# rx.net
KiCad netlist of a schematic drawn in EAGLE
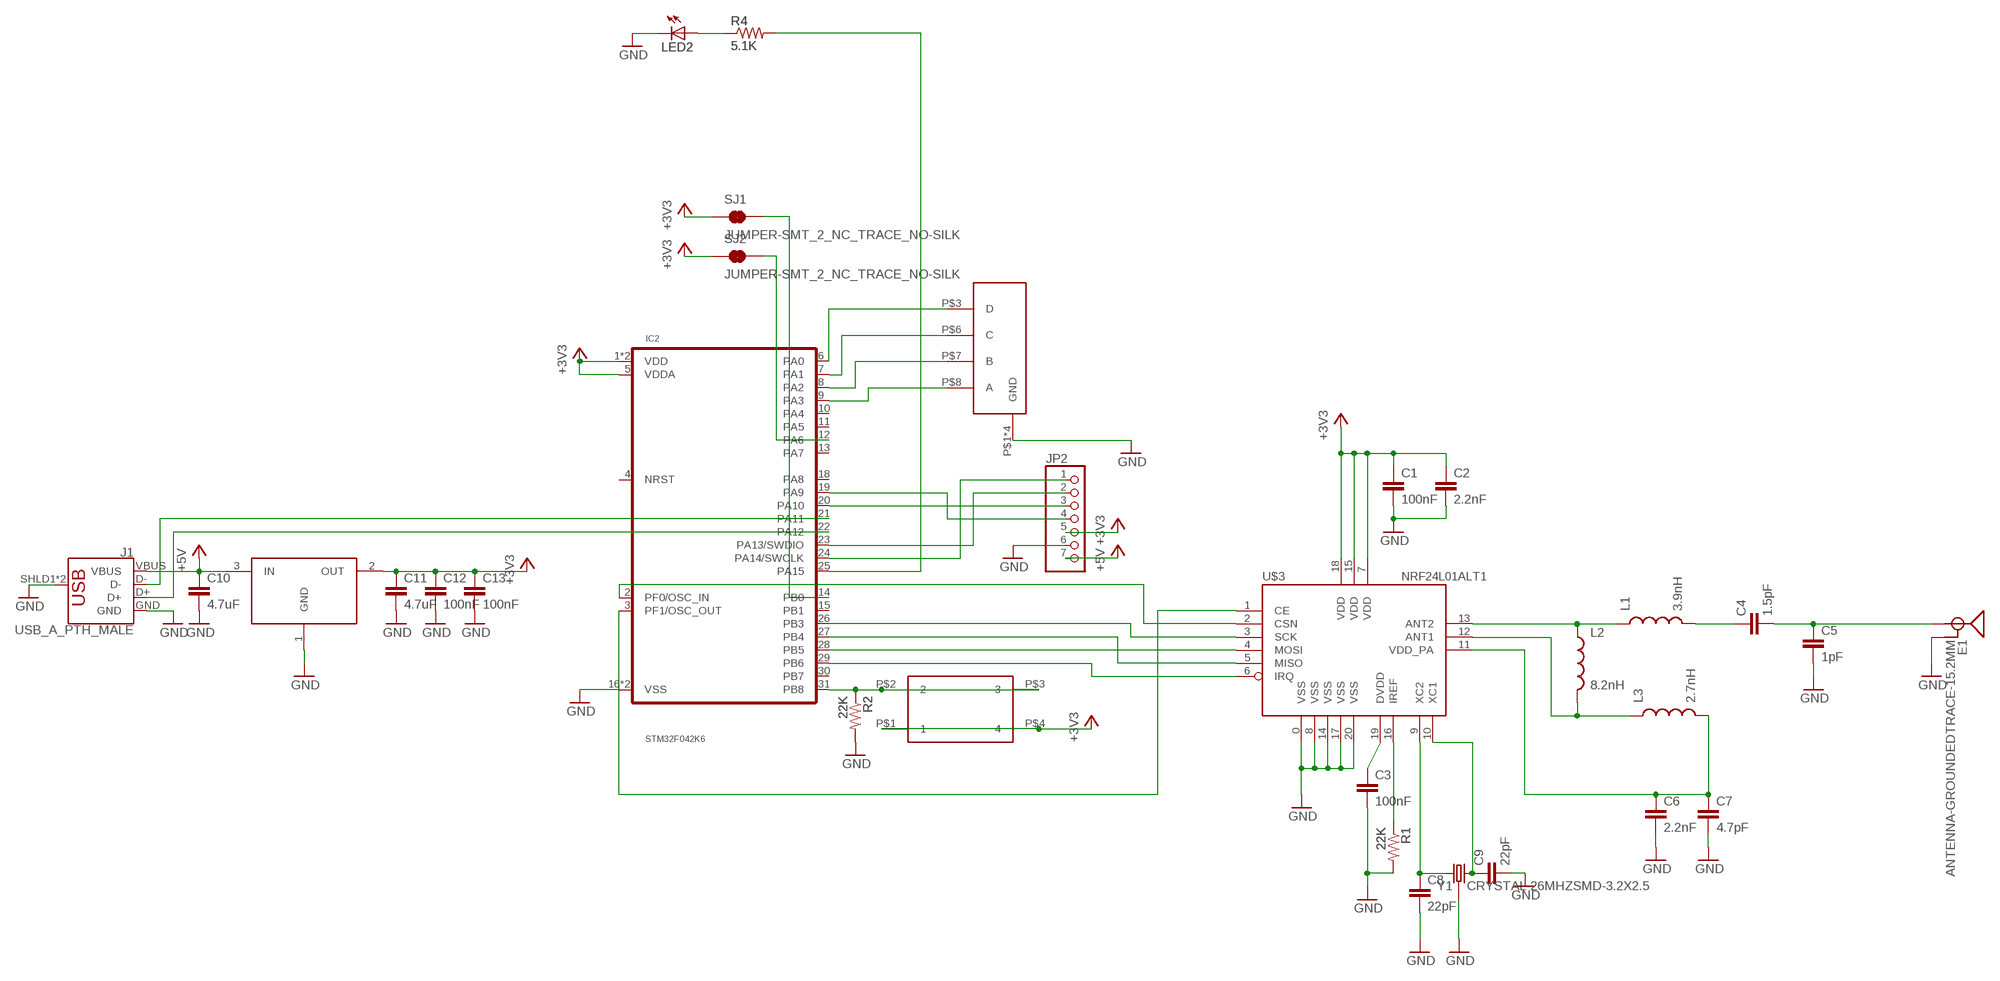
[diagram p0: schematic, sheet 1]

(export (version "E")
  (design (tool "Eeschema 10.0.6"))
  (components
    (comp (ref "C1")
      (value "100nF")
      (footprint "eagle-import:0805")
      (libsource (lib "eagle-import") (part "CAP0805"))
    )
    (comp (ref "C2")
      (value "2.2nF")
      (footprint "eagle-import:0805")
      (libsource (lib "eagle-import") (part "CAP0805"))
    )
    (comp (ref "C3")
      (value "100nF")
      (footprint "eagle-import:0805")
      (libsource (lib "eagle-import") (part "CAP0805"))
    )
    (comp (ref "C4")
      (value "1.5pF")
      (footprint "eagle-import:0805")
      (libsource (lib "eagle-import") (part "CAP0805"))
    )
    (comp (ref "C5")
      (value "1pF")
      (footprint "eagle-import:0805")
      (libsource (lib "eagle-import") (part "CAP0805"))
    )
    (comp (ref "C6")
      (value "2.2nF")
      (footprint "eagle-import:0805")
      (libsource (lib "eagle-import") (part "CAP0805"))
    )
    (comp (ref "C7")
      (value "4.7pF")
      (footprint "eagle-import:0805")
      (libsource (lib "eagle-import") (part "CAP0805"))
    )
    (comp (ref "C8")
      (value "22pF")
      (footprint "eagle-import:0805")
      (libsource (lib "eagle-import") (part "CAP0805"))
    )
    (comp (ref "C9")
      (value "22pF")
      (footprint "eagle-import:0805")
      (libsource (lib "eagle-import") (part "CAP0805"))
    )
    (comp (ref "C10")
      (value "4.7uF")
      (footprint "eagle-import:0805")
      (libsource (lib "eagle-import") (part "CAP0805"))
    )
    (comp (ref "C11")
      (value "4.7uF")
      (footprint "eagle-import:0805")
      (libsource (lib "eagle-import") (part "CAP0805"))
    )
    (comp (ref "C12")
      (value "100nF")
      (footprint "eagle-import:0805")
      (libsource (lib "eagle-import") (part "CAP0805"))
    )
    (comp (ref "C13")
      (value "100nF")
      (footprint "eagle-import:0805")
      (libsource (lib "eagle-import") (part "CAP0805"))
    )
    (comp (ref "E1")
      (value "ANTENNA-GROUNDEDTRACE-15.2MM")
      (footprint "eagle-import:TRACE_ANTENNA_2.4GHZ_15.2MM")
      (libsource (lib "eagle-import") (part "ANTENNA-GROUNDEDTRACE-15.2MM"))
    )
    (comp (ref "IC2")
      (value "STM32F042K6")
      (footprint "eagle-import:TQFP32-08")
      (libsource (lib "eagle-import") (part "STM32F042K6"))
    )
    (comp (ref "J1")
      (value "USB_A_PTH_MALE")
      (footprint "eagle-import:USB-A-H")
      (libsource (lib "eagle-import") (part "USB_A_PTH_MALE"))
    )
    (comp (ref "JP2")
      (value "PINHD-1X8CLEANBIG")
      (footprint "eagle-import:1X08-CLEANBIG")
      (libsource (lib "eagle-import") (part "PINHD-1X8CLEANBIG"))
    )
    (comp (ref "L1")
      (value "3.9nH")
      (footprint "eagle-import:0805")
      (libsource (lib "eagle-import") (part "INDUCTOR0805"))
    )
    (comp (ref "L2")
      (value "8.2nH")
      (footprint "eagle-import:0805")
      (libsource (lib "eagle-import") (part "INDUCTOR0805"))
    )
    (comp (ref "L3")
      (value "2.7nH")
      (footprint "eagle-import:0805")
      (libsource (lib "eagle-import") (part "INDUCTOR0805"))
    )
    (comp (ref "LED2")
      (value "LEDCHIP-LED0805")
      (footprint "eagle-import:CHIP-LED0805")
      (libsource (lib "eagle-import") (part "LEDCHIP-LED0805"))
    )
    (comp (ref "R1")
      (value "22K")
      (footprint "eagle-import:0805")
      (libsource (lib "eagle-import") (part "RESISTOR0805-RES"))
    )
    (comp (ref "R2")
      (value "22K")
      (footprint "eagle-import:0805")
      (libsource (lib "eagle-import") (part "RESISTOR0805-RES"))
    )
    (comp (ref "R4")
      (value "5.1K")
      (footprint "eagle-import:0805")
      (libsource (lib "eagle-import") (part "RESISTOR0805-RES"))
    )
    (comp (ref "SJ1")
      (value "JUMPER-SMT_2_NC_TRACE_NO-SILK")
      (footprint "eagle-import:SMT-JUMPER_2_NC_TRACE_NO-SILK")
      (libsource (lib "eagle-import") (part "JUMPER-SMT_2_NC_TRACE_NO-SILK"))
    )
    (comp (ref "SJ2")
      (value "JUMPER-SMT_2_NC_TRACE_NO-SILK")
      (footprint "eagle-import:SMT-JUMPER_2_NC_TRACE_NO-SILK")
      (libsource (lib "eagle-import") (part "JUMPER-SMT_2_NC_TRACE_NO-SILK"))
    )
    (comp (ref "U$1")
      (value "SW_3POS_DEVSW_3POS_OFFICIAL")
      (footprint "eagle-import:SW_3POS_FOOT_OFFICIAL")
      (libsource (lib "eagle-import") (part "SW_3POS_DEVSW_3POS_OFFICIAL"))
    )
    (comp (ref "U$3")
      (value "NRF24L01ALT1")
      (footprint "eagle-import:QFN20_ALT1")
      (libsource (lib "eagle-import") (part "NRF24L01ALT1"))
    )
    (comp (ref "U$4")
      (value "XC6206_DEV")
      (footprint "eagle-import:SOT23R_INFINEON")
      (libsource (lib "eagle-import") (part "XC6206_DEV"))
    )
    (comp (ref "U$10")
      (value "324_SW")
      (footprint "eagle-import:342_SWICH_FOOT")
      (libsource (lib "eagle-import") (part "324_SW"))
    )
    (comp (ref "Y1")
      (value "CRYSTAL-26MHZSMD-3.2X2.5")
      (footprint "eagle-import:CRYSTAL-SMD-3.2X2.5MM")
      (libsource (lib "eagle-import") (part "CRYSTAL-26MHZSMD-3.2X2.5"))
    )
  )
  (nets
    (net (code "1") (name "+3V3") (class "Default")
      (node (ref "C1") (pin "1") (pinfunction "1_1") (pintype "passive"))
      (node (ref "C11") (pin "1") (pinfunction "1_1") (pintype "passive"))
      (node (ref "C12") (pin "1") (pinfunction "1_1") (pintype "passive"))
      (node (ref "C13") (pin "1") (pinfunction "1_1") (pintype "passive"))
      (node (ref "C2") (pin "1") (pinfunction "1_1") (pintype "passive"))
      (node (ref "IC2") (pin "1") (pinfunction "VDD_1") (pintype "bidirectional"))
      (node (ref "IC2") (pin "17") (pinfunction "VDD_17") (pintype "bidirectional"))
      (node (ref "IC2") (pin "5") (pinfunction "VDDA_5") (pintype "bidirectional"))
      (node (ref "JP2") (pin "5") (pinfunction "5_5") (pintype "passive"))
      (node (ref "SJ1") (pin "1") (pinfunction "1_1") (pintype "passive"))
      (node (ref "SJ2") (pin "1") (pinfunction "1_1") (pintype "passive"))
      (node (ref "U$10") (pin "P$1") (pinfunction "1_P$1") (pintype "bidirectional"))
      (node (ref "U$10") (pin "P$4") (pinfunction "4_P$4") (pintype "bidirectional"))
      (node (ref "U$3") (pin "15") (pinfunction "VDD_15") (pintype "power_in"))
      (node (ref "U$3") (pin "18") (pinfunction "VDD_18") (pintype "power_in"))
      (node (ref "U$3") (pin "7") (pinfunction "VDD_7") (pintype "power_in"))
      (node (ref "U$4") (pin "2") (pinfunction "OUT_2") (pintype "bidirectional"))
    )
    (net (code "2") (name "+5V") (class "Default")
      (node (ref "C10") (pin "1") (pinfunction "1_1") (pintype "passive"))
      (node (ref "J1") (pin "VBUS") (pinfunction "VBUS_VBUS") (pintype "power_in"))
      (node (ref "JP2") (pin "7") (pinfunction "7_7") (pintype "passive"))
      (node (ref "U$4") (pin "3") (pinfunction "IN_3") (pintype "bidirectional"))
    )
    (net (code "3") (name "GND") (class "Default")
      (node (ref "C1") (pin "2") (pinfunction "2_2") (pintype "passive"))
      (node (ref "C10") (pin "2") (pinfunction "2_2") (pintype "passive"))
      (node (ref "C11") (pin "2") (pinfunction "2_2") (pintype "passive"))
      (node (ref "C12") (pin "2") (pinfunction "2_2") (pintype "passive"))
      (node (ref "C13") (pin "2") (pinfunction "2_2") (pintype "passive"))
      (node (ref "C2") (pin "2") (pinfunction "2_2") (pintype "passive"))
      (node (ref "C3") (pin "2") (pinfunction "2_2") (pintype "passive"))
      (node (ref "C5") (pin "2") (pinfunction "2_2") (pintype "passive"))
      (node (ref "C6") (pin "2") (pinfunction "2_2") (pintype "passive"))
      (node (ref "C7") (pin "2") (pinfunction "2_2") (pintype "passive"))
      (node (ref "C8") (pin "2") (pinfunction "2_2") (pintype "passive"))
      (node (ref "C9") (pin "2") (pinfunction "2_2") (pintype "passive"))
      (node (ref "E1") (pin "GND") (pinfunction "GND_GND") (pintype "bidirectional"))
      (node (ref "IC2") (pin "16") (pinfunction "VSS_16") (pintype "bidirectional"))
      (node (ref "IC2") (pin "32") (pinfunction "VSS_32") (pintype "bidirectional"))
      (node (ref "J1") (pin "GND") (pinfunction "GND_GND") (pintype "power_in"))
      (node (ref "J1") (pin "SHLD1") (pinfunction "SHIELD_SHLD1") (pintype "bidirectional"))
      (node (ref "J1") (pin "SHLD2") (pinfunction "SHIELD_SHLD2") (pintype "bidirectional"))
      (node (ref "JP2") (pin "6") (pinfunction "6_6") (pintype "passive"))
      (node (ref "LED2") (pin "C") (pinfunction "C_C") (pintype "passive"))
      (node (ref "R1") (pin "2") (pinfunction "2_2") (pintype "passive"))
      (node (ref "R2") (pin "2") (pinfunction "2_2") (pintype "passive"))
      (node (ref "U$1") (pin "P$1") (pinfunction "GND_P$1") (pintype "bidirectional"))
      (node (ref "U$1") (pin "P$2") (pinfunction "GND_P$2") (pintype "bidirectional"))
      (node (ref "U$1") (pin "P$4") (pinfunction "GND_P$4") (pintype "bidirectional"))
      (node (ref "U$1") (pin "P$5") (pinfunction "GND_P$5") (pintype "bidirectional"))
      (node (ref "U$3") (pin "0") (pinfunction "VSS_0") (pintype "power_in"))
      (node (ref "U$3") (pin "14") (pinfunction "VSS_14") (pintype "power_in"))
      (node (ref "U$3") (pin "17") (pinfunction "VSS_17") (pintype "power_in"))
      (node (ref "U$3") (pin "20") (pinfunction "VSS_20") (pintype "power_in"))
      (node (ref "U$3") (pin "8") (pinfunction "VSS_8") (pintype "power_in"))
      (node (ref "U$4") (pin "1") (pinfunction "GND_1") (pintype "bidirectional"))
      (node (ref "Y1") (pin "2") (pinfunction "3_2") (pintype "passive"))
      (node (ref "Y1") (pin "4") (pinfunction "3_4") (pintype "passive"))
    )
    (net (code "4") (name "Net-(C4-Pad1)") (class "Default")
      (node (ref "C4") (pin "1") (pinfunction "1_1") (pintype "passive"))
      (node (ref "L1") (pin "2") (pinfunction "2_2") (pintype "passive"))
    )
    (net (code "5") (name "Net-(E1-SIGNAL)") (class "Default")
      (node (ref "C4") (pin "2") (pinfunction "2_2") (pintype "passive"))
      (node (ref "C5") (pin "1") (pinfunction "1_1") (pintype "passive"))
      (node (ref "E1") (pin "ANT") (pinfunction "SIGNAL_ANT") (pintype "bidirectional"))
    )
    (net (code "6") (name "Net-(IC2-PA0)") (class "Default")
      (node (ref "IC2") (pin "6") (pinfunction "PA0_6") (pintype "bidirectional"))
      (node (ref "U$1") (pin "P$3") (pinfunction "D_P$3") (pintype "bidirectional"))
    )
    (net (code "7") (name "Net-(IC2-PA1)") (class "Default")
      (node (ref "IC2") (pin "7") (pinfunction "PA1_7") (pintype "bidirectional"))
      (node (ref "U$1") (pin "P$6") (pinfunction "C_P$6") (pintype "bidirectional"))
    )
    (net (code "8") (name "Net-(IC2-PA2)") (class "Default")
      (node (ref "IC2") (pin "8") (pinfunction "PA2_8") (pintype "bidirectional"))
      (node (ref "U$1") (pin "P$7") (pinfunction "B_P$7") (pintype "bidirectional"))
    )
    (net (code "9") (name "Net-(IC2-PA3)") (class "Default")
      (node (ref "IC2") (pin "9") (pinfunction "PA3_9") (pintype "bidirectional"))
      (node (ref "U$1") (pin "P$8") (pinfunction "A_P$8") (pintype "bidirectional"))
    )
    (net (code "10") (name "Net-(IC2-PA6)") (class "Default")
      (node (ref "IC2") (pin "12") (pinfunction "PA6_12") (pintype "bidirectional"))
      (node (ref "SJ2") (pin "2") (pinfunction "2_2") (pintype "passive"))
    )
    (net (code "11") (name "Net-(IC2-PA9)") (class "Default")
      (node (ref "IC2") (pin "19") (pinfunction "PA9_19") (pintype "bidirectional"))
      (node (ref "JP2") (pin "4") (pinfunction "4_4") (pintype "passive"))
    )
    (net (code "12") (name "Net-(IC2-PA10)") (class "Default")
      (node (ref "IC2") (pin "20") (pinfunction "PA10_20") (pintype "bidirectional"))
      (node (ref "JP2") (pin "3") (pinfunction "3_3") (pintype "passive"))
    )
    (net (code "13") (name "Net-(IC2-PA11)") (class "Default")
      (node (ref "IC2") (pin "21") (pinfunction "PA11_21") (pintype "bidirectional"))
      (node (ref "J1") (pin "D-") (pinfunction "D-_D-") (pintype "bidirectional"))
    )
    (net (code "14") (name "Net-(IC2-PA12)") (class "Default")
      (node (ref "IC2") (pin "22") (pinfunction "PA12_22") (pintype "bidirectional"))
      (node (ref "J1") (pin "D+") (pinfunction "D+_D+") (pintype "bidirectional"))
    )
    (net (code "15") (name "Net-(IC2-PA13{slash}SWDIO)") (class "Default")
      (node (ref "IC2") (pin "23") (pinfunction "PA13/SWDIO_23") (pintype "bidirectional"))
      (node (ref "JP2") (pin "2") (pinfunction "2_2") (pintype "passive"))
    )
    (net (code "16") (name "Net-(IC2-PA14{slash}SWCLK)") (class "Default")
      (node (ref "IC2") (pin "24") (pinfunction "PA14/SWCLK_24") (pintype "bidirectional"))
      (node (ref "JP2") (pin "1") (pinfunction "1_1") (pintype "passive"))
    )
    (net (code "17") (name "Net-(IC2-PA15)") (class "Default")
      (node (ref "IC2") (pin "25") (pinfunction "PA15_25") (pintype "bidirectional"))
      (node (ref "R4") (pin "2") (pinfunction "2_2") (pintype "passive"))
    )
    (net (code "18") (name "Net-(IC2-PB0)") (class "Default")
      (node (ref "IC2") (pin "14") (pinfunction "PB0_14") (pintype "bidirectional"))
      (node (ref "SJ1") (pin "2") (pinfunction "2_2") (pintype "passive"))
    )
    (net (code "19") (name "Net-(IC2-PB3)") (class "Default")
      (node (ref "IC2") (pin "26") (pinfunction "PB3_26") (pintype "bidirectional"))
      (node (ref "U$3") (pin "3") (pinfunction "SCK_3") (pintype "input"))
    )
    (net (code "20") (name "Net-(IC2-PB4)") (class "Default")
      (node (ref "IC2") (pin "27") (pinfunction "PB4_27") (pintype "bidirectional"))
      (node (ref "U$3") (pin "5") (pinfunction "MISO_5") (pintype "output"))
    )
    (net (code "21") (name "Net-(IC2-PB5)") (class "Default")
      (node (ref "IC2") (pin "28") (pinfunction "PB5_28") (pintype "bidirectional"))
      (node (ref "U$3") (pin "4") (pinfunction "MOSI_4") (pintype "input"))
    )
    (net (code "22") (name "Net-(IC2-PB6)") (class "Default")
      (node (ref "IC2") (pin "29") (pinfunction "PB6_29") (pintype "bidirectional"))
      (node (ref "U$3") (pin "6") (pinfunction "IRQ_6") (pintype "output"))
    )
    (net (code "23") (name "Net-(IC2-PB8)") (class "Default")
      (node (ref "IC2") (pin "31") (pinfunction "PB8_31") (pintype "bidirectional"))
      (node (ref "R2") (pin "1") (pinfunction "1_1") (pintype "passive"))
      (node (ref "U$10") (pin "P$2") (pinfunction "2_P$2") (pintype "bidirectional"))
      (node (ref "U$10") (pin "P$3") (pinfunction "3_P$3") (pintype "bidirectional"))
    )
    (net (code "24") (name "Net-(IC2-PF0{slash}OSC_IN)") (class "Default")
      (node (ref "IC2") (pin "2") (pinfunction "PF0/OSC_IN_2") (pintype "bidirectional"))
      (node (ref "U$3") (pin "2") (pinfunction "CSN_2") (pintype "input"))
    )
    (net (code "25") (name "Net-(IC2-PF1{slash}OSC_OUT)") (class "Default")
      (node (ref "IC2") (pin "3") (pinfunction "PF1/OSC_OUT_3") (pintype "bidirectional"))
      (node (ref "U$3") (pin "1") (pinfunction "CE_1") (pintype "input"))
    )
    (net (code "26") (name "Net-(LED2-PadA)") (class "Default")
      (node (ref "LED2") (pin "A") (pinfunction "A_A") (pintype "passive"))
      (node (ref "R4") (pin "1") (pinfunction "1_1") (pintype "passive"))
    )
    (net (code "27") (name "Net-(U$3-ANT1)") (class "Default")
      (node (ref "L2") (pin "2") (pinfunction "2_2") (pintype "passive"))
      (node (ref "L3") (pin "1") (pinfunction "1_1") (pintype "passive"))
      (node (ref "U$3") (pin "12") (pinfunction "ANT1_12") (pintype "output"))
    )
    (net (code "28") (name "Net-(U$3-ANT2)") (class "Default")
      (node (ref "L1") (pin "1") (pinfunction "1_1") (pintype "passive"))
      (node (ref "L2") (pin "1") (pinfunction "1_1") (pintype "passive"))
      (node (ref "U$3") (pin "13") (pinfunction "ANT2_13") (pintype "output"))
    )
    (net (code "29") (name "Net-(U$3-DVDD)") (class "Default")
      (node (ref "C3") (pin "1") (pinfunction "1_1") (pintype "passive"))
      (node (ref "U$3") (pin "19") (pinfunction "DVDD_19") (pintype "power_in"))
    )
    (net (code "30") (name "Net-(U$3-IREF)") (class "Default")
      (node (ref "R1") (pin "1") (pinfunction "1_1") (pintype "passive"))
      (node (ref "U$3") (pin "16") (pinfunction "IREF_16") (pintype "input"))
    )
    (net (code "31") (name "Net-(U$3-VDD_PA)") (class "Default")
      (node (ref "C6") (pin "1") (pinfunction "1_1") (pintype "passive"))
      (node (ref "C7") (pin "1") (pinfunction "1_1") (pintype "passive"))
      (node (ref "L3") (pin "2") (pinfunction "2_2") (pintype "passive"))
      (node (ref "U$3") (pin "11") (pinfunction "VDD_PA_11") (pintype "power_in"))
    )
    (net (code "32") (name "Net-(U$3-XC1)") (class "Default")
      (node (ref "C9") (pin "1") (pinfunction "1_1") (pintype "passive"))
      (node (ref "U$3") (pin "10") (pinfunction "XC1_10") (pintype "input"))
      (node (ref "Y1") (pin "3") (pinfunction "2_3") (pintype "passive"))
    )
    (net (code "33") (name "Net-(U$3-XC2)") (class "Default")
      (node (ref "C8") (pin "1") (pinfunction "1_1") (pintype "passive"))
      (node (ref "U$3") (pin "9") (pinfunction "XC2_9") (pintype "input"))
      (node (ref "Y1") (pin "1") (pinfunction "1_1") (pintype "passive"))
    )
    (net (code "34") (name "unconnected-(IC2-NRST-Pad4)") (class "Default")
      (node (ref "IC2") (pin "4") (pinfunction "NRST_4") (pintype "bidirectional"))
    )
    (net (code "35") (name "unconnected-(IC2-PA4-Pad10)") (class "Default")
      (node (ref "IC2") (pin "10") (pinfunction "PA4_10") (pintype "bidirectional"))
    )
    (net (code "36") (name "unconnected-(IC2-PA5-Pad11)") (class "Default")
      (node (ref "IC2") (pin "11") (pinfunction "PA5_11") (pintype "bidirectional"))
    )
    (net (code "37") (name "unconnected-(IC2-PA7-Pad13)") (class "Default")
      (node (ref "IC2") (pin "13") (pinfunction "PA7_13") (pintype "bidirectional"))
    )
    (net (code "38") (name "unconnected-(IC2-PA8-Pad18)") (class "Default")
      (node (ref "IC2") (pin "18") (pinfunction "PA8_18") (pintype "bidirectional"))
    )
    (net (code "39") (name "unconnected-(IC2-PB1-Pad15)") (class "Default")
      (node (ref "IC2") (pin "15") (pinfunction "PB1_15") (pintype "bidirectional"))
    )
    (net (code "40") (name "unconnected-(IC2-PB7-Pad30)") (class "Default")
      (node (ref "IC2") (pin "30") (pinfunction "PB7_30") (pintype "bidirectional"))
    )
  )
)
